# UI.net
KiCad netlist of a schematic drawn in Altium Designer
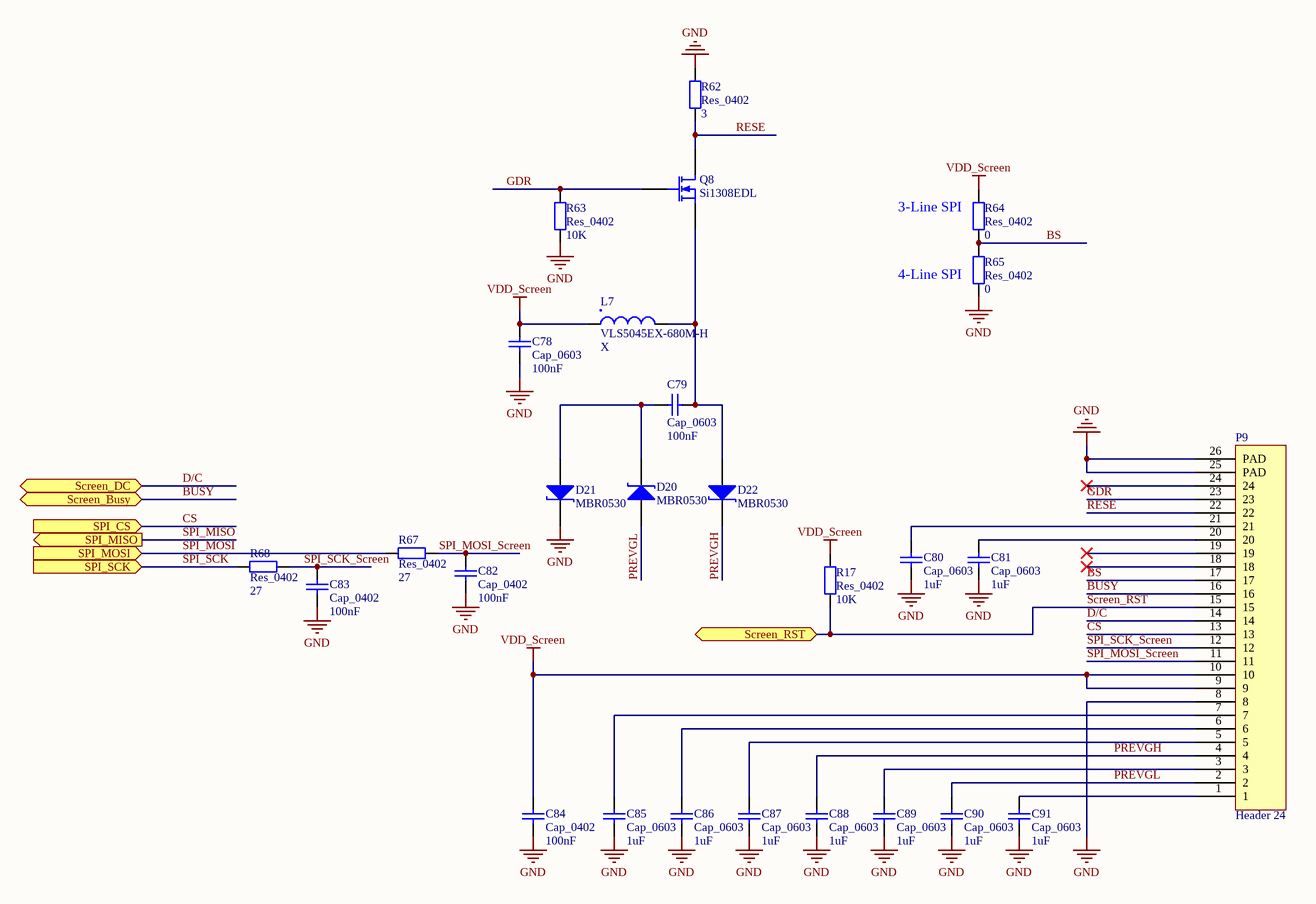
[diagram p0: UI.SchDoc]

(export (version "E")
  (design (tool "Eeschema 10.0.6"))
  (components
    (comp (ref "C78")
      (value "Cap_0603")
      (footprint "0603")
      (description "Capacitor")
      (fields (field (name "ALTIUM_VALUE") "100nF") (field (name "PUBLISHER") "Altium Limited"))
      (libsource (lib "Schematic_Components") (part "Cap_0603"))
    )
    (comp (ref "C79")
      (value "Cap_0603")
      (footprint "0603")
      (description "Capacitor")
      (fields (field (name "ALTIUM_VALUE") "100nF") (field (name "PUBLISHER") "Altium Limited"))
      (libsource (lib "Schematic_Components") (part "Cap_0603"))
    )
    (comp (ref "C80")
      (value "Cap_0603")
      (footprint "0603")
      (description "Capacitor")
      (fields (field (name "ALTIUM_VALUE") "1uF") (field (name "PUBLISHER") "Altium Limited"))
      (libsource (lib "Schematic_Components") (part "Cap_0603"))
    )
    (comp (ref "C81")
      (value "Cap_0603")
      (footprint "0603")
      (description "Capacitor")
      (fields (field (name "ALTIUM_VALUE") "1uF") (field (name "PUBLISHER") "Altium Limited"))
      (libsource (lib "Schematic_Components") (part "Cap_0603"))
    )
    (comp (ref "C82")
      (value "Cap_0402")
      (footprint "0402")
      (description "Capacitor")
      (fields (field (name "ALTIUM_VALUE") "100nF") (field (name "PUBLISHER") "Altium Limited"))
      (libsource (lib "Schematic_Components") (part "Cap_0402"))
    )
    (comp (ref "C83")
      (value "Cap_0402")
      (footprint "0402")
      (description "Capacitor")
      (fields (field (name "ALTIUM_VALUE") "100nF") (field (name "PUBLISHER") "Altium Limited"))
      (libsource (lib "Schematic_Components") (part "Cap_0402"))
    )
    (comp (ref "C84")
      (value "Cap_0402")
      (footprint "0402")
      (description "Capacitor")
      (fields (field (name "ALTIUM_VALUE") "100nF") (field (name "PUBLISHER") "Altium Limited"))
      (libsource (lib "Schematic_Components") (part "Cap_0402"))
    )
    (comp (ref "C85")
      (value "Cap_0603")
      (footprint "0603")
      (description "Capacitor")
      (fields (field (name "ALTIUM_VALUE") "1uF") (field (name "PUBLISHER") "Altium Limited"))
      (libsource (lib "Schematic_Components") (part "Cap_0603"))
    )
    (comp (ref "C86")
      (value "Cap_0603")
      (footprint "0603")
      (description "Capacitor")
      (fields (field (name "ALTIUM_VALUE") "1uF") (field (name "PUBLISHER") "Altium Limited"))
      (libsource (lib "Schematic_Components") (part "Cap_0603"))
    )
    (comp (ref "C87")
      (value "Cap_0603")
      (footprint "0603")
      (description "Capacitor")
      (fields (field (name "ALTIUM_VALUE") "1uF") (field (name "PUBLISHER") "Altium Limited"))
      (libsource (lib "Schematic_Components") (part "Cap_0603"))
    )
    (comp (ref "C88")
      (value "Cap_0603")
      (footprint "0603")
      (description "Capacitor")
      (fields (field (name "ALTIUM_VALUE") "1uF") (field (name "PUBLISHER") "Altium Limited"))
      (libsource (lib "Schematic_Components") (part "Cap_0603"))
    )
    (comp (ref "C89")
      (value "Cap_0603")
      (footprint "0603")
      (description "Capacitor")
      (fields (field (name "ALTIUM_VALUE") "1uF") (field (name "PUBLISHER") "Altium Limited"))
      (libsource (lib "Schematic_Components") (part "Cap_0603"))
    )
    (comp (ref "C90")
      (value "Cap_0603")
      (footprint "0603")
      (description "Capacitor")
      (fields (field (name "ALTIUM_VALUE") "1uF") (field (name "PUBLISHER") "Altium Limited"))
      (libsource (lib "Schematic_Components") (part "Cap_0603"))
    )
    (comp (ref "C91")
      (value "Cap_0603")
      (footprint "0603")
      (description "Capacitor")
      (fields (field (name "ALTIUM_VALUE") "1uF") (field (name "PUBLISHER") "Altium Limited"))
      (libsource (lib "Schematic_Components") (part "Cap_0603"))
    )
    (comp (ref "D20")
      (value "MBR0530")
      (footprint "SOD-123")
      (description "SCHOTTKY BARRIER\r\nRECTIFIER")
      (fields (field (name "PUBLISHER") "Altium Limited"))
      (libsource (lib "Schematic_Components") (part "MBR0530"))
    )
    (comp (ref "D21")
      (value "MBR0530")
      (footprint "SOD-123")
      (description "SCHOTTKY BARRIER\r\nRECTIFIER")
      (fields (field (name "PUBLISHER") "Altium Limited"))
      (libsource (lib "Schematic_Components") (part "MBR0530"))
    )
    (comp (ref "D22")
      (value "MBR0530")
      (footprint "SOD-123")
      (description "SCHOTTKY BARRIER\r\nRECTIFIER")
      (fields (field (name "PUBLISHER") "Altium Limited"))
      (libsource (lib "Schematic_Components") (part "MBR0530"))
    )
    (comp (ref "L7")
      (value "VLS5045EX-680M-H")
      (footprint "VLS5045EX")
      (description "Inductor 68 uH")
      (fields (field (name "ALTIUM_VALUE") "X"))
      (libsource (lib "Schematic_Components") (part "VLS5045EX-680M-H"))
    )
    (comp (ref "P9")
      (value "Header 24")
      (footprint "Flex_EInc_Connector")
      (description "Header, 24-Pin")
      (fields (field (name "PUBLISHER") "Altium Limited"))
      (libsource (lib "Schematic_Components") (part "Header 24"))
    )
    (comp (ref "Q8")
      (value "Si1308EDL")
      (footprint "SOT-23")
      (description "N-Channel MOSFET")
      (fields (field (name "PUBLISHER") "Altium Limited"))
      (libsource (lib "Schematic_Components") (part "Si1308EDL"))
    )
    (comp (ref "R17")
      (value "Res_0402")
      (footprint "0402")
      (description "Resistor")
      (fields (field (name "ALTIUM_VALUE") "10K") (field (name "PUBLISHER") "Altium Limited"))
      (libsource (lib "") (part "Res_0402_1"))
    )
    (comp (ref "R62")
      (value "Res_0402")
      (footprint "0402")
      (description "Resistor")
      (fields (field (name "ALTIUM_VALUE") "3") (field (name "PUBLISHER") "Altium Limited"))
      (libsource (lib "") (part "Res_0402_1"))
    )
    (comp (ref "R63")
      (value "Res_0402")
      (footprint "0402")
      (description "Resistor")
      (fields (field (name "ALTIUM_VALUE") "10K") (field (name "PUBLISHER") "Altium Limited"))
      (libsource (lib "") (part "Res_0402_1"))
    )
    (comp (ref "R64")
      (value "Res_0402")
      (footprint "0402")
      (description "Resistor")
      (fields (field (name "ALTIUM_VALUE") "0") (field (name "PUBLISHER") "Altium Limited"))
      (libsource (lib "") (part "Res_0402_1"))
    )
    (comp (ref "R65")
      (value "Res_0402")
      (footprint "0402")
      (description "Resistor")
      (fields (field (name "ALTIUM_VALUE") "0") (field (name "PUBLISHER") "Altium Limited"))
      (libsource (lib "") (part "Res_0402_1"))
    )
    (comp (ref "R67")
      (value "Res_0402")
      (footprint "0402")
      (description "Resistor")
      (fields (field (name "ALTIUM_VALUE") "27") (field (name "PUBLISHER") "Altium Limited"))
      (libsource (lib "Schematic_Components") (part "Res_0402"))
    )
    (comp (ref "R68")
      (value "Res_0402")
      (footprint "0402")
      (description "Resistor")
      (fields (field (name "ALTIUM_VALUE") "27") (field (name "PUBLISHER") "Altium Limited"))
      (libsource (lib "Schematic_Components") (part "Res_0402"))
    )
  )
  (nets
    (net (code "1") (name "/BS") (class "Default")
      (node (ref "P9") (pin "17") (pinfunction "17_17") (pintype "passive"))
      (node (ref "R64") (pin "1") (pinfunction "1_1") (pintype "passive"))
      (node (ref "R65") (pin "2") (pinfunction "2_2") (pintype "passive"))
    )
    (net (code "2") (name "/BUSY") (class "Default")
      (node (ref "P9") (pin "16") (pinfunction "16_16") (pintype "passive"))
    )
    (net (code "3") (name "/CS") (class "Default")
      (node (ref "P9") (pin "13") (pinfunction "13_13") (pintype "passive"))
    )
    (net (code "4") (name "/D{slash}C") (class "Default")
      (node (ref "P9") (pin "14") (pinfunction "14_14") (pintype "passive"))
    )
    (net (code "5") (name "/GDR") (class "Default")
      (node (ref "P9") (pin "23") (pinfunction "23_23") (pintype "passive"))
      (node (ref "Q8") (pin "1") (pinfunction "G_1") (pintype "passive"))
      (node (ref "R63") (pin "2") (pinfunction "2_2") (pintype "passive"))
    )
    (net (code "6") (name "/PREVGH") (class "Default")
      (node (ref "C88") (pin "2") (pinfunction "2_2") (pintype "passive"))
      (node (ref "D22") (pin "1") (pinfunction "K_1") (pintype "passive"))
      (node (ref "P9") (pin "4") (pinfunction "4_4") (pintype "passive"))
    )
    (net (code "7") (name "/PREVGL") (class "Default")
      (node (ref "C90") (pin "2") (pinfunction "2_2") (pintype "passive"))
      (node (ref "D20") (pin "2") (pinfunction "A_2") (pintype "passive"))
      (node (ref "P9") (pin "2") (pinfunction "2_2") (pintype "passive"))
    )
    (net (code "8") (name "/RESE") (class "Default")
      (node (ref "P9") (pin "22") (pinfunction "22_22") (pintype "passive"))
      (node (ref "Q8") (pin "3") (pinfunction "D_3") (pintype "passive"))
      (node (ref "R62") (pin "1") (pinfunction "1_1") (pintype "passive"))
    )
    (net (code "10") (name "/SPI_MOSI") (class "Default")
      (node (ref "R67") (pin "1") (pinfunction "1_1") (pintype "passive"))
    )
    (net (code "11") (name "/SPI_MOSI_Screen") (class "Default")
      (node (ref "C82") (pin "2") (pinfunction "2_2") (pintype "passive"))
      (node (ref "P9") (pin "11") (pinfunction "11_11") (pintype "passive"))
      (node (ref "R67") (pin "2") (pinfunction "2_2") (pintype "passive"))
    )
    (net (code "12") (name "/SPI_SCK") (class "Default")
      (node (ref "R68") (pin "1") (pinfunction "1_1") (pintype "passive"))
    )
    (net (code "13") (name "/SPI_SCK_Screen") (class "Default")
      (node (ref "C83") (pin "2") (pinfunction "2_2") (pintype "passive"))
      (node (ref "P9") (pin "12") (pinfunction "12_12") (pintype "passive"))
      (node (ref "R68") (pin "2") (pinfunction "2_2") (pintype "passive"))
    )
    (net (code "14") (name "/Screen_RST") (class "Default")
      (node (ref "P9") (pin "15") (pinfunction "15_15") (pintype "passive"))
      (node (ref "R17") (pin "1") (pinfunction "1_1") (pintype "passive"))
    )
    (net (code "15") (name "GND") (class "Default")
      (node (ref "C78") (pin "1") (pinfunction "1_1") (pintype "passive"))
      (node (ref "C80") (pin "1") (pinfunction "1_1") (pintype "passive"))
      (node (ref "C81") (pin "1") (pinfunction "1_1") (pintype "passive"))
      (node (ref "C82") (pin "1") (pinfunction "1_1") (pintype "passive"))
      (node (ref "C83") (pin "1") (pinfunction "1_1") (pintype "passive"))
      (node (ref "C84") (pin "1") (pinfunction "1_1") (pintype "passive"))
      (node (ref "C85") (pin "1") (pinfunction "1_1") (pintype "passive"))
      (node (ref "C86") (pin "1") (pinfunction "1_1") (pintype "passive"))
      (node (ref "C87") (pin "1") (pinfunction "1_1") (pintype "passive"))
      (node (ref "C88") (pin "1") (pinfunction "1_1") (pintype "passive"))
      (node (ref "C89") (pin "1") (pinfunction "1_1") (pintype "passive"))
      (node (ref "C90") (pin "1") (pinfunction "1_1") (pintype "passive"))
      (node (ref "C91") (pin "1") (pinfunction "1_1") (pintype "passive"))
      (node (ref "D21") (pin "1") (pinfunction "K_1") (pintype "passive"))
      (node (ref "P9") (pin "25") (pinfunction "PAD_25") (pintype "passive"))
      (node (ref "P9") (pin "26") (pinfunction "PAD_26") (pintype "passive"))
      (node (ref "P9") (pin "8") (pinfunction "8_8") (pintype "passive"))
      (node (ref "R62") (pin "2") (pinfunction "2_2") (pintype "passive"))
      (node (ref "R63") (pin "1") (pinfunction "1_1") (pintype "passive"))
      (node (ref "R65") (pin "1") (pinfunction "1_1") (pintype "passive"))
    )
    (net (code "16") (name "Net-(C80-Pad2)") (class "Default")
      (node (ref "C80") (pin "2") (pinfunction "2_2") (pintype "passive"))
      (node (ref "P9") (pin "21") (pinfunction "21_21") (pintype "passive"))
    )
    (net (code "17") (name "Net-(C81-Pad2)") (class "Default")
      (node (ref "C81") (pin "2") (pinfunction "2_2") (pintype "passive"))
      (node (ref "P9") (pin "20") (pinfunction "20_20") (pintype "passive"))
    )
    (net (code "18") (name "Net-(C85-Pad2)") (class "Default")
      (node (ref "C85") (pin "2") (pinfunction "2_2") (pintype "passive"))
      (node (ref "P9") (pin "7") (pinfunction "7_7") (pintype "passive"))
    )
    (net (code "19") (name "Net-(C86-Pad2)") (class "Default")
      (node (ref "C86") (pin "2") (pinfunction "2_2") (pintype "passive"))
      (node (ref "P9") (pin "6") (pinfunction "6_6") (pintype "passive"))
    )
    (net (code "20") (name "Net-(C87-Pad2)") (class "Default")
      (node (ref "C87") (pin "2") (pinfunction "2_2") (pintype "passive"))
      (node (ref "P9") (pin "5") (pinfunction "5_5") (pintype "passive"))
    )
    (net (code "21") (name "Net-(C89-Pad2)") (class "Default")
      (node (ref "C89") (pin "2") (pinfunction "2_2") (pintype "passive"))
      (node (ref "P9") (pin "3") (pinfunction "3_3") (pintype "passive"))
    )
    (net (code "22") (name "Net-(C91-Pad2)") (class "Default")
      (node (ref "C91") (pin "2") (pinfunction "2_2") (pintype "passive"))
      (node (ref "P9") (pin "1") (pinfunction "1_1") (pintype "passive"))
    )
    (net (code "23") (name "Net-(D20-K)") (class "Default")
      (node (ref "C79") (pin "1") (pinfunction "1_1") (pintype "passive"))
      (node (ref "D20") (pin "1") (pinfunction "K_1") (pintype "passive"))
      (node (ref "D21") (pin "2") (pinfunction "A_2") (pintype "passive"))
    )
    (net (code "24") (name "Net-(D22-A)") (class "Default")
      (node (ref "C79") (pin "2") (pinfunction "2_2") (pintype "passive"))
      (node (ref "D22") (pin "2") (pinfunction "A_2") (pintype "passive"))
      (node (ref "L7") (pin "2") (pinfunction "2_2") (pintype "passive"))
      (node (ref "Q8") (pin "2") (pinfunction "S_2") (pintype "passive"))
    )
    (net (code "25") (name "VDD_Screen") (class "Default")
      (node (ref "C78") (pin "2") (pinfunction "2_2") (pintype "passive"))
      (node (ref "C84") (pin "2") (pinfunction "2_2") (pintype "passive"))
      (node (ref "L7") (pin "1") (pinfunction "1_1") (pintype "passive"))
      (node (ref "P9") (pin "10") (pinfunction "10_10") (pintype "passive"))
      (node (ref "P9") (pin "9") (pinfunction "9_9") (pintype "passive"))
      (node (ref "R17") (pin "2") (pinfunction "2_2") (pintype "passive"))
      (node (ref "R64") (pin "2") (pinfunction "2_2") (pintype "passive"))
    )
    (net (code "26") (name "unconnected-(P9-Pad18)") (class "Default")
      (node (ref "P9") (pin "18") (pinfunction "18_18") (pintype "passive+no_connect"))
    )
    (net (code "27") (name "unconnected-(P9-Pad19)") (class "Default")
      (node (ref "P9") (pin "19") (pinfunction "19_19") (pintype "passive+no_connect"))
    )
    (net (code "28") (name "unconnected-(P9-Pad24)") (class "Default")
      (node (ref "P9") (pin "24") (pinfunction "24_24") (pintype "passive+no_connect"))
    )
  )
)
